# digidog-v3.net
KiCad netlist of a schematic drawn in EAGLE
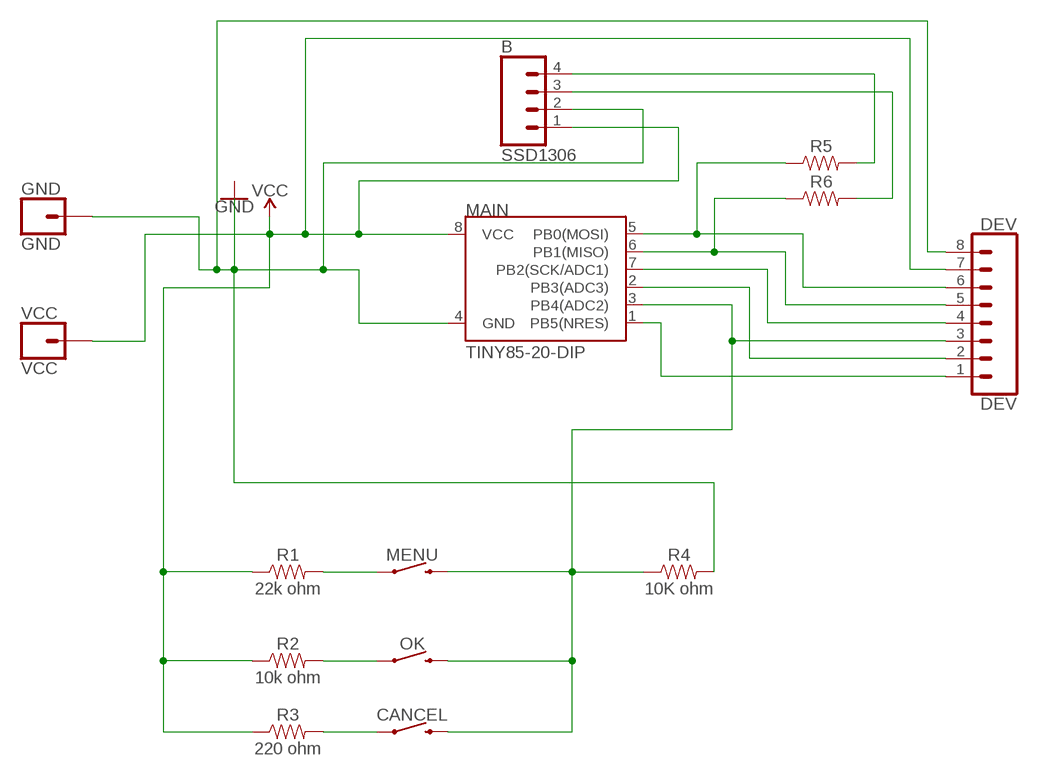
[diagram p0: schematic, sheet 1]

(export (version "E")
  (design (tool "Eeschema 10.0.6"))
  (components
    (comp (ref "B")
      (value "SSD1306")
      (footprint "eagle-import:1X04")
      (libsource (lib "eagle-import") (part "CONN_04"))
    )
    (comp (ref "CANCEL")
      (value "MOMENTARY-SWITCH-SPST-PTH-6.0MM")
      (footprint "eagle-import:TACTILE_SWITCH_PTH_6.0MM")
      (libsource (lib "eagle-import") (part "MOMENTARY-SWITCH-SPST-PTH-6.0MM"))
    )
    (comp (ref "DEV")
      (value "DEV")
      (footprint "eagle-import:1X08")
      (libsource (lib "eagle-import") (part "CONN_08{dblquote}"))
    )
    (comp (ref "GND")
      (value "GND")
      (footprint "eagle-import:1X01")
      (libsource (lib "eagle-import") (part "CONN_01"))
    )
    (comp (ref "MAIN")
      (value "TINY85-20-DIP")
      (footprint "eagle-import:DIP08_MCU")
      (libsource (lib "eagle-import") (part "ATTINY45TINY85-20-DIP"))
    )
    (comp (ref "MENU")
      (value "MOMENTARY-SWITCH-SPST-PTH-6.0MM")
      (footprint "eagle-import:TACTILE_SWITCH_PTH_6.0MM")
      (libsource (lib "eagle-import") (part "MOMENTARY-SWITCH-SPST-PTH-6.0MM"))
    )
    (comp (ref "OK")
      (value "MOMENTARY-SWITCH-SPST-PTH-6.0MM")
      (footprint "eagle-import:TACTILE_SWITCH_PTH_6.0MM")
      (libsource (lib "eagle-import") (part "MOMENTARY-SWITCH-SPST-PTH-6.0MM"))
    )
    (comp (ref "R1")
      (value "22k ohm")
      (footprint "eagle-import:AXIAL-0.3")
      (libsource (lib "eagle-import") (part "RESISTORAXIAL-0.3"))
    )
    (comp (ref "R2")
      (value "10k ohm")
      (footprint "eagle-import:AXIAL-0.3")
      (libsource (lib "eagle-import") (part "RESISTORAXIAL-0.3"))
    )
    (comp (ref "R3")
      (value "220 ohm")
      (footprint "eagle-import:AXIAL-0.3")
      (libsource (lib "eagle-import") (part "RESISTORAXIAL-0.3"))
    )
    (comp (ref "R4")
      (value "10K ohm")
      (footprint "eagle-import:AXIAL-0.3")
      (libsource (lib "eagle-import") (part "RESISTORAXIAL-0.3"))
    )
    (comp (ref "R5")
      (value "RESISTORAXIAL-0.3")
      (footprint "eagle-import:AXIAL-0.3")
      (libsource (lib "eagle-import") (part "RESISTORAXIAL-0.3"))
    )
    (comp (ref "R6")
      (value "RESISTORAXIAL-0.3")
      (footprint "eagle-import:AXIAL-0.3")
      (libsource (lib "eagle-import") (part "RESISTORAXIAL-0.3"))
    )
    (comp (ref "VCC")
      (value "VCC")
      (footprint "eagle-import:1X01")
      (libsource (lib "eagle-import") (part "CONN_01"))
    )
  )
  (nets
    (net (code "2") (name "Net-(CANCEL-2)") (class "Default")
      (node (ref "CANCEL") (pin "3") (pinfunction "2_3") (pintype "passive"))
      (node (ref "DEV") (pin "3") (pinfunction "3_3") (pintype "passive"))
      (node (ref "MAIN") (pin "3") (pinfunction "PB4(ADC2)_3") (pintype "bidirectional"))
      (node (ref "MENU") (pin "3") (pinfunction "2_3") (pintype "passive"))
      (node (ref "OK") (pin "3") (pinfunction "2_3") (pintype "passive"))
      (node (ref "R4") (pin "P$1") (pinfunction "1_P$1") (pintype "passive"))
    )
    (net (code "3") (name "Net-(MAIN-GND)") (class "Default")
      (node (ref "B") (pin "2") (pinfunction "2_2") (pintype "passive"))
      (node (ref "DEV") (pin "8") (pinfunction "8_8") (pintype "passive"))
      (node (ref "GND") (pin "1") (pinfunction "1_1") (pintype "passive"))
      (node (ref "MAIN") (pin "4") (pinfunction "GND_4") (pintype "bidirectional"))
      (node (ref "R4") (pin "P$2") (pinfunction "2_P$2") (pintype "passive"))
    )
    (net (code "4") (name "Net-(MAIN-PB0(MOSI))") (class "Default")
      (node (ref "DEV") (pin "6") (pinfunction "6_6") (pintype "passive"))
      (node (ref "MAIN") (pin "5") (pinfunction "PB0(MOSI)_5") (pintype "bidirectional"))
      (node (ref "R5") (pin "P$1") (pinfunction "1_P$1") (pintype "passive"))
    )
    (net (code "5") (name "Net-(MAIN-PB1(MISO))") (class "Default")
      (node (ref "DEV") (pin "5") (pinfunction "5_5") (pintype "passive"))
      (node (ref "MAIN") (pin "6") (pinfunction "PB1(MISO)_6") (pintype "bidirectional"))
      (node (ref "R6") (pin "P$1") (pinfunction "1_P$1") (pintype "passive"))
    )
    (net (code "6") (name "Net-(MAIN-PB2(SCK{slash}ADC1))") (class "Default")
      (node (ref "DEV") (pin "4") (pinfunction "4_4") (pintype "passive"))
      (node (ref "MAIN") (pin "7") (pinfunction "PB2(SCK/ADC1)_7") (pintype "bidirectional"))
    )
    (net (code "7") (name "Net-(MAIN-PB3(ADC3))") (class "Default")
      (node (ref "DEV") (pin "2") (pinfunction "2_2") (pintype "passive"))
      (node (ref "MAIN") (pin "2") (pinfunction "PB3(ADC3)_2") (pintype "bidirectional"))
    )
    (net (code "8") (name "Net-(MAIN-PB5(NRES))") (class "Default")
      (node (ref "DEV") (pin "1") (pinfunction "1_1") (pintype "passive"))
      (node (ref "MAIN") (pin "1") (pinfunction "PB5(NRES)_1") (pintype "bidirectional"))
    )
    (net (code "9") (name "Net-(R1-2)") (class "Default")
      (node (ref "MENU") (pin "1") (pinfunction "1_1") (pintype "passive"))
      (node (ref "R1") (pin "P$2") (pinfunction "2_P$2") (pintype "passive"))
    )
    (net (code "10") (name "Net-(R2-2)") (class "Default")
      (node (ref "OK") (pin "1") (pinfunction "1_1") (pintype "passive"))
      (node (ref "R2") (pin "P$2") (pinfunction "2_P$2") (pintype "passive"))
    )
    (net (code "11") (name "Net-(R3-2)") (class "Default")
      (node (ref "CANCEL") (pin "1") (pinfunction "1_1") (pintype "passive"))
      (node (ref "R3") (pin "P$2") (pinfunction "2_P$2") (pintype "passive"))
    )
    (net (code "12") (name "Net-(R5-2)") (class "Default")
      (node (ref "B") (pin "4") (pinfunction "4_4") (pintype "passive"))
      (node (ref "R5") (pin "P$2") (pinfunction "2_P$2") (pintype "passive"))
    )
    (net (code "13") (name "Net-(R6-2)") (class "Default")
      (node (ref "B") (pin "3") (pinfunction "3_3") (pintype "passive"))
      (node (ref "R6") (pin "P$2") (pinfunction "2_P$2") (pintype "passive"))
    )
    (net (code "14") (name "VCC") (class "Default")
      (node (ref "B") (pin "1") (pinfunction "1_1") (pintype "passive"))
      (node (ref "DEV") (pin "7") (pinfunction "7_7") (pintype "passive"))
      (node (ref "MAIN") (pin "8") (pinfunction "VCC_8") (pintype "bidirectional"))
      (node (ref "R1") (pin "P$1") (pinfunction "1_P$1") (pintype "passive"))
      (node (ref "R2") (pin "P$1") (pinfunction "1_P$1") (pintype "passive"))
      (node (ref "R3") (pin "P$1") (pinfunction "1_P$1") (pintype "passive"))
      (node (ref "VCC") (pin "1") (pinfunction "1_1") (pintype "passive"))
    )
  )
)
